# mosfet_shield.net
KiCad netlist of a schematic drawn in EAGLE
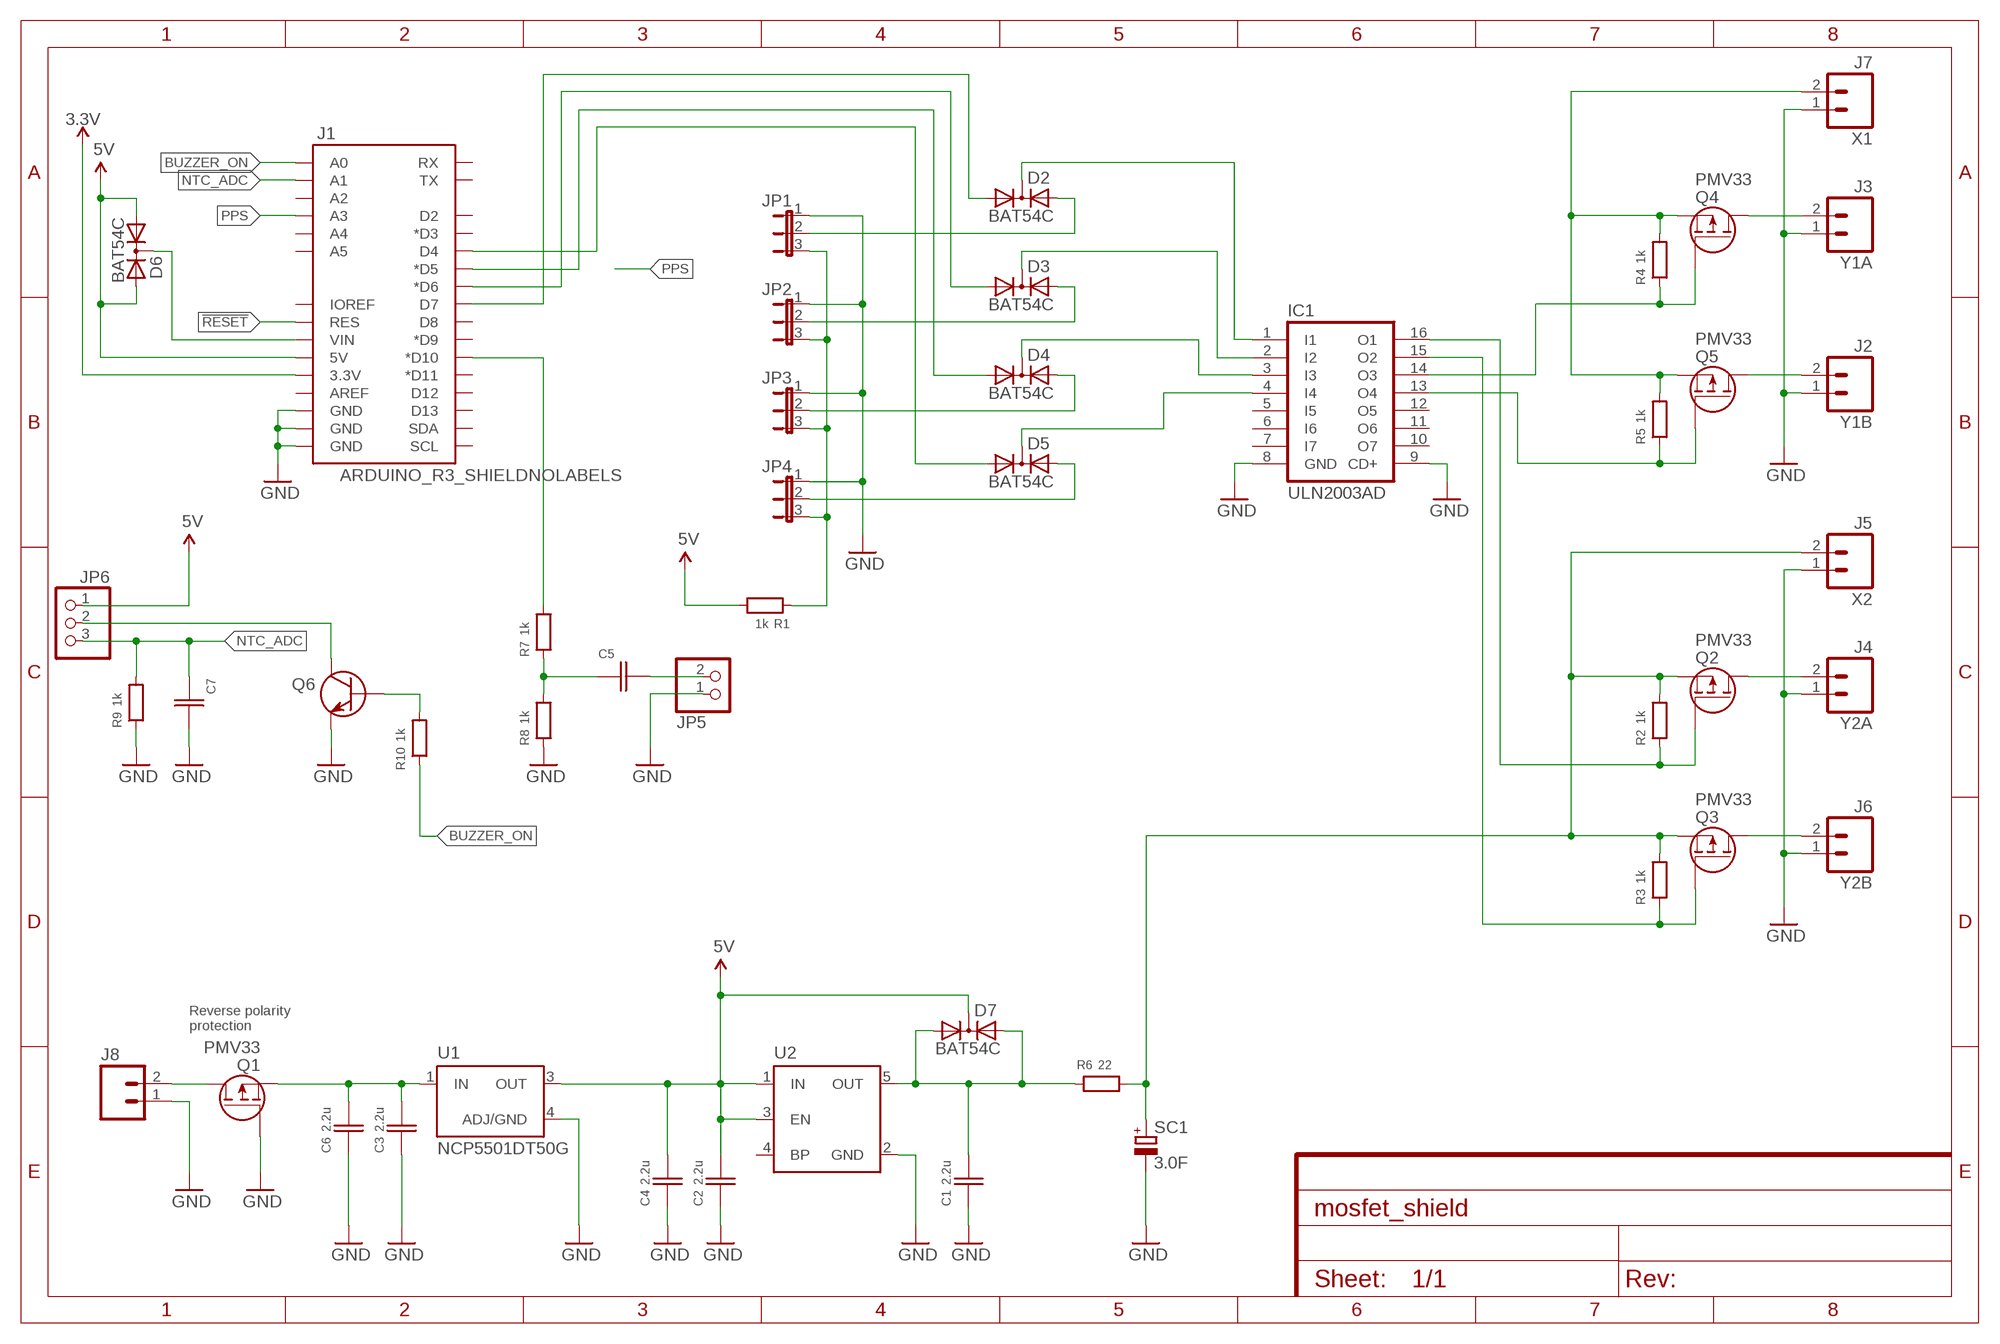
[diagram p0: schematic, sheet 1]

(export (version "E")
  (design (tool "Eeschema 10.0.6"))
  (components
    (comp (ref "C1")
      (value "2.2u")
      (footprint "eagle-import:C1206")
      (libsource (lib "eagle-import") (part "CAPACITOR_NPOL-1206"))
    )
    (comp (ref "C2")
      (value "2.2u")
      (footprint "eagle-import:C1206")
      (libsource (lib "eagle-import") (part "CAPACITOR_NPOL-1206"))
    )
    (comp (ref "C3")
      (value "2.2u")
      (footprint "eagle-import:C1206")
      (libsource (lib "eagle-import") (part "CAPACITOR_NPOL-1206"))
    )
    (comp (ref "C4")
      (value "2.2u")
      (footprint "eagle-import:C1206")
      (libsource (lib "eagle-import") (part "CAPACITOR_NPOL-1206"))
    )
    (comp (ref "C5")
      (value "CAPACITOR_NPOL-0603")
      (footprint "eagle-import:C603")
      (libsource (lib "eagle-import") (part "CAPACITOR_NPOL-0603"))
    )
    (comp (ref "C6")
      (value "2.2u")
      (footprint "eagle-import:C1206")
      (libsource (lib "eagle-import") (part "CAPACITOR_NPOL-1206"))
    )
    (comp (ref "C7")
      (value "CAPACITOR_NPOL-0603")
      (footprint "eagle-import:C603")
      (libsource (lib "eagle-import") (part "CAPACITOR_NPOL-0603"))
    )
    (comp (ref "D2")
      (value "BAT54C")
      (footprint "eagle-import:SOT23")
      (libsource (lib "eagle-import") (part "DIODE-2AC|CASOT23"))
    )
    (comp (ref "D3")
      (value "BAT54C")
      (footprint "eagle-import:SOT23")
      (libsource (lib "eagle-import") (part "DIODE-2AC|CASOT23"))
    )
    (comp (ref "D4")
      (value "BAT54C")
      (footprint "eagle-import:SOT23")
      (libsource (lib "eagle-import") (part "DIODE-2AC|CASOT23"))
    )
    (comp (ref "D5")
      (value "BAT54C")
      (footprint "eagle-import:SOT23")
      (libsource (lib "eagle-import") (part "DIODE-2AC|CASOT23"))
    )
    (comp (ref "D6")
      (value "BAT54C")
      (footprint "eagle-import:SOT23")
      (libsource (lib "eagle-import") (part "DIODE-2AC|CASOT23"))
    )
    (comp (ref "D7")
      (value "BAT54C")
      (footprint "eagle-import:SOT23")
      (libsource (lib "eagle-import") (part "DIODE-2AC|CASOT23"))
    )
    (comp (ref "IC1")
      (value "ULN2003AD")
      (footprint "eagle-import:SO16")
      (libsource (lib "eagle-import") (part "ULN2003AD"))
    )
    (comp (ref "J1")
      (value "ARDUINO_R3_SHIELDNOLABELS")
      (footprint "eagle-import:UNO_R3_SHIELD_NOLABELS")
      (libsource (lib "eagle-import") (part "ARDUINO_R3_SHIELDNOLABELS"))
    )
    (comp (ref "J2")
      (value "Y1B")
      (footprint "eagle-import:SCREWTERMINAL-3.5MM-2")
      (libsource (lib "eagle-import") (part "M023.5MM"))
    )
    (comp (ref "J3")
      (value "Y1A")
      (footprint "eagle-import:SCREWTERMINAL-3.5MM-2")
      (libsource (lib "eagle-import") (part "M023.5MM"))
    )
    (comp (ref "J4")
      (value "Y2A")
      (footprint "eagle-import:SCREWTERMINAL-3.5MM-2")
      (libsource (lib "eagle-import") (part "M023.5MM"))
    )
    (comp (ref "J5")
      (value "X2")
      (footprint "eagle-import:SCREWTERMINAL-3.5MM-2")
      (libsource (lib "eagle-import") (part "M023.5MM"))
    )
    (comp (ref "J6")
      (value "Y2B")
      (footprint "eagle-import:SCREWTERMINAL-3.5MM-2")
      (libsource (lib "eagle-import") (part "M023.5MM"))
    )
    (comp (ref "J7")
      (value "X1")
      (footprint "eagle-import:SCREWTERMINAL-3.5MM-2")
      (libsource (lib "eagle-import") (part "M023.5MM"))
    )
    (comp (ref "J8")
      (value "M023.5MM")
      (footprint "eagle-import:SCREWTERMINAL-3.5MM-2")
      (libsource (lib "eagle-import") (part "M023.5MM"))
    )
    (comp (ref "JP1")
      (value "JP2E")
      (footprint "eagle-import:JP2")
      (libsource (lib "eagle-import") (part "JP2E"))
    )
    (comp (ref "JP2")
      (value "JP2E")
      (footprint "eagle-import:JP2")
      (libsource (lib "eagle-import") (part "JP2E"))
    )
    (comp (ref "JP3")
      (value "JP2E")
      (footprint "eagle-import:JP2")
      (libsource (lib "eagle-import") (part "JP2E"))
    )
    (comp (ref "JP4")
      (value "JP2E")
      (footprint "eagle-import:JP2")
      (libsource (lib "eagle-import") (part "JP2E"))
    )
    (comp (ref "JP5")
      (value "PINHD-1X2")
      (footprint "eagle-import:1X02")
      (libsource (lib "eagle-import") (part "PINHD-1X2"))
    )
    (comp (ref "JP6")
      (value "PINHD-1X3")
      (footprint "eagle-import:1X03")
      (libsource (lib "eagle-import") (part "PINHD-1X3"))
    )
    (comp (ref "Q1")
      (value "PMV33")
      (footprint "eagle-import:SOT23-3")
      (libsource (lib "eagle-import") (part "MOSFET-P-SOT23-3"))
    )
    (comp (ref "Q2")
      (value "PMV33")
      (footprint "eagle-import:SOT23-3")
      (libsource (lib "eagle-import") (part "MOSFET-P-SOT23-3"))
    )
    (comp (ref "Q3")
      (value "PMV33")
      (footprint "eagle-import:SOT23-3")
      (libsource (lib "eagle-import") (part "MOSFET-P-SOT23-3"))
    )
    (comp (ref "Q4")
      (value "PMV33")
      (footprint "eagle-import:SOT23-3")
      (libsource (lib "eagle-import") (part "MOSFET-P-SOT23-3"))
    )
    (comp (ref "Q5")
      (value "PMV33")
      (footprint "eagle-import:SOT23-3")
      (libsource (lib "eagle-import") (part "MOSFET-P-SOT23-3"))
    )
    (comp (ref "Q6")
      (value "BJT-NPN-SOT23-3")
      (footprint "eagle-import:SOT23-3")
      (libsource (lib "eagle-import") (part "BJT-NPN-SOT23-3"))
    )
    (comp (ref "R1")
      (value "1k")
      (footprint "eagle-import:R0603")
      (libsource (lib "eagle-import") (part "RESISTOR-0603"))
    )
    (comp (ref "R2")
      (value "1k")
      (footprint "eagle-import:R0603")
      (libsource (lib "eagle-import") (part "RESISTOR-0603"))
    )
    (comp (ref "R3")
      (value "1k")
      (footprint "eagle-import:R0603")
      (libsource (lib "eagle-import") (part "RESISTOR-0603"))
    )
    (comp (ref "R4")
      (value "1k")
      (footprint "eagle-import:R0603")
      (libsource (lib "eagle-import") (part "RESISTOR-0603"))
    )
    (comp (ref "R5")
      (value "1k")
      (footprint "eagle-import:R0603")
      (libsource (lib "eagle-import") (part "RESISTOR-0603"))
    )
    (comp (ref "R6")
      (value "22")
      (footprint "eagle-import:R0603")
      (libsource (lib "eagle-import") (part "RESISTOR-0603"))
    )
    (comp (ref "R7")
      (value "1k")
      (footprint "eagle-import:R0603")
      (libsource (lib "eagle-import") (part "RESISTOR-0603"))
    )
    (comp (ref "R8")
      (value "1k")
      (footprint "eagle-import:R0603")
      (libsource (lib "eagle-import") (part "RESISTOR-0603"))
    )
    (comp (ref "R9")
      (value "1k")
      (footprint "eagle-import:R0603")
      (libsource (lib "eagle-import") (part "RESISTOR-0603"))
    )
    (comp (ref "R10")
      (value "1k")
      (footprint "eagle-import:R0603")
      (libsource (lib "eagle-import") (part "RESISTOR-0603"))
    )
    (comp (ref "SC1")
      (value "3.0F")
      (footprint "eagle-import:E3,5-8")
      (libsource (lib "eagle-import") (part "CPOL-EUE3.5-8"))
    )
    (comp (ref "U1")
      (value "NCP5501DT50G")
      (footprint "eagle-import:DPAK")
      (libsource (lib "eagle-import") (part "VREG-3PIN-DPAK"))
    )
    (comp (ref "U2")
      (value "VREG-5PIN-SOT23")
      (footprint "eagle-import:SOT23-5")
      (libsource (lib "eagle-import") (part "VREG-5PIN-SOT23"))
    )
  )
  (nets
    (net (code "1") (name "/~{RESET}") (class "Default")
      (node (ref "J1") (pin "RES") (pinfunction "RES_RES") (pintype "bidirectional"))
    )
    (net (code "2") (name "3.3V") (class "Default")
      (node (ref "J1") (pin "3.3V") (pinfunction "3.3V_3.3V") (pintype "bidirectional"))
    )
    (net (code "3") (name "5V") (class "Default")
      (node (ref "C2") (pin "2") (pinfunction "2_2") (pintype "passive"))
      (node (ref "C4") (pin "2") (pinfunction "2_2") (pintype "passive"))
      (node (ref "D6") (pin "1") (pinfunction "A1_1") (pintype "passive"))
      (node (ref "D6") (pin "2") (pinfunction "A2_2") (pintype "passive"))
      (node (ref "D7") (pin "3") (pinfunction "C_3") (pintype "passive"))
      (node (ref "J1") (pin "5V") (pinfunction "5V_5V") (pintype "bidirectional"))
      (node (ref "JP6") (pin "1") (pinfunction "1_1") (pintype "passive"))
      (node (ref "R1") (pin "2") (pinfunction "2_2") (pintype "passive"))
      (node (ref "U1") (pin "3") (pinfunction "OUT_3") (pintype "bidirectional"))
      (node (ref "U2") (pin "1") (pinfunction "IN_1") (pintype "bidirectional"))
      (node (ref "U2") (pin "3") (pinfunction "EN_3") (pintype "bidirectional"))
    )
    (net (code "4") (name "BUZZER_ON") (class "Default")
      (node (ref "J1") (pin "A0") (pinfunction "A0_A0") (pintype "bidirectional"))
      (node (ref "R10") (pin "1") (pinfunction "1_1") (pintype "passive"))
    )
    (net (code "5") (name "GND") (class "Default")
      (node (ref "C1") (pin "1") (pinfunction "1_1") (pintype "passive"))
      (node (ref "C2") (pin "1") (pinfunction "1_1") (pintype "passive"))
      (node (ref "C3") (pin "1") (pinfunction "1_1") (pintype "passive"))
      (node (ref "C4") (pin "1") (pinfunction "1_1") (pintype "passive"))
      (node (ref "C6") (pin "1") (pinfunction "1_1") (pintype "passive"))
      (node (ref "C7") (pin "2") (pinfunction "2_2") (pintype "passive"))
      (node (ref "IC1") (pin "8") (pinfunction "GND_8") (pintype "power_in"))
      (node (ref "IC1") (pin "9") (pinfunction "CD+_9") (pintype "passive"))
      (node (ref "J1") (pin "GND@0") (pinfunction "GND_GND@0") (pintype "bidirectional"))
      (node (ref "J1") (pin "GND@1") (pinfunction "GND_GND@1") (pintype "bidirectional"))
      (node (ref "J1") (pin "GND@2") (pinfunction "GND_GND@2") (pintype "bidirectional"))
      (node (ref "J2") (pin "1") (pinfunction "1_1") (pintype "passive"))
      (node (ref "J3") (pin "1") (pinfunction "1_1") (pintype "passive"))
      (node (ref "J4") (pin "1") (pinfunction "1_1") (pintype "passive"))
      (node (ref "J5") (pin "1") (pinfunction "1_1") (pintype "passive"))
      (node (ref "J6") (pin "1") (pinfunction "1_1") (pintype "passive"))
      (node (ref "J7") (pin "1") (pinfunction "1_1") (pintype "passive"))
      (node (ref "J8") (pin "1") (pinfunction "1_1") (pintype "passive"))
      (node (ref "JP1") (pin "1") (pinfunction "1_1") (pintype "passive"))
      (node (ref "JP2") (pin "1") (pinfunction "1_1") (pintype "passive"))
      (node (ref "JP3") (pin "1") (pinfunction "1_1") (pintype "passive"))
      (node (ref "JP4") (pin "1") (pinfunction "1_1") (pintype "passive"))
      (node (ref "JP5") (pin "1") (pinfunction "1_1") (pintype "passive"))
      (node (ref "Q1") (pin "1") (pinfunction "G_1") (pintype "passive"))
      (node (ref "Q6") (pin "2") (pinfunction "E_2") (pintype "passive"))
      (node (ref "R8") (pin "1") (pinfunction "1_1") (pintype "passive"))
      (node (ref "R9") (pin "1") (pinfunction "1_1") (pintype "passive"))
      (node (ref "SC1") (pin "-") (pinfunction "-_-") (pintype "passive"))
      (node (ref "U1") (pin "4") (pinfunction "ADJ/GND_4") (pintype "bidirectional"))
      (node (ref "U2") (pin "2") (pinfunction "GND_2") (pintype "bidirectional"))
    )
    (net (code "6") (name "NTC_ADC") (class "Default")
      (node (ref "C7") (pin "1") (pinfunction "1_1") (pintype "passive"))
      (node (ref "J1") (pin "A1") (pinfunction "A1_A1") (pintype "bidirectional"))
      (node (ref "JP6") (pin "3") (pinfunction "3_3") (pintype "passive"))
      (node (ref "R9") (pin "2") (pinfunction "2_2") (pintype "passive"))
    )
    (net (code "7") (name "Net-(C5-Pad1)") (class "Default")
      (node (ref "C5") (pin "1") (pinfunction "1_1") (pintype "passive"))
      (node (ref "R7") (pin "1") (pinfunction "1_1") (pintype "passive"))
      (node (ref "R8") (pin "2") (pinfunction "2_2") (pintype "passive"))
    )
    (net (code "8") (name "Net-(C5-Pad2)") (class "Default")
      (node (ref "C5") (pin "2") (pinfunction "2_2") (pintype "passive"))
      (node (ref "JP5") (pin "2") (pinfunction "2_2") (pintype "passive"))
    )
    (net (code "9") (name "Net-(D2-A1)") (class "Default")
      (node (ref "D2") (pin "1") (pinfunction "A1_1") (pintype "passive"))
      (node (ref "J1") (pin "D7") (pinfunction "D7_D7") (pintype "bidirectional"))
    )
    (net (code "10") (name "Net-(D2-A2)") (class "Default")
      (node (ref "D2") (pin "2") (pinfunction "A2_2") (pintype "passive"))
      (node (ref "JP1") (pin "2") (pinfunction "2_2") (pintype "passive"))
    )
    (net (code "11") (name "Net-(D2-C)") (class "Default")
      (node (ref "D2") (pin "3") (pinfunction "C_3") (pintype "passive"))
      (node (ref "IC1") (pin "1") (pinfunction "I1_1") (pintype "input"))
    )
    (net (code "12") (name "Net-(D3-A1)") (class "Default")
      (node (ref "D3") (pin "1") (pinfunction "A1_1") (pintype "passive"))
      (node (ref "J1") (pin "D6") (pinfunction "*D6_D6") (pintype "bidirectional"))
    )
    (net (code "13") (name "Net-(D3-A2)") (class "Default")
      (node (ref "D3") (pin "2") (pinfunction "A2_2") (pintype "passive"))
      (node (ref "JP2") (pin "2") (pinfunction "2_2") (pintype "passive"))
    )
    (net (code "14") (name "Net-(D3-C)") (class "Default")
      (node (ref "D3") (pin "3") (pinfunction "C_3") (pintype "passive"))
      (node (ref "IC1") (pin "2") (pinfunction "I2_2") (pintype "input"))
    )
    (net (code "15") (name "Net-(D4-A1)") (class "Default")
      (node (ref "D4") (pin "1") (pinfunction "A1_1") (pintype "passive"))
      (node (ref "J1") (pin "D5") (pinfunction "*D5_D5") (pintype "bidirectional"))
    )
    (net (code "16") (name "Net-(D4-A2)") (class "Default")
      (node (ref "D4") (pin "2") (pinfunction "A2_2") (pintype "passive"))
      (node (ref "JP3") (pin "2") (pinfunction "2_2") (pintype "passive"))
    )
    (net (code "17") (name "Net-(D4-C)") (class "Default")
      (node (ref "D4") (pin "3") (pinfunction "C_3") (pintype "passive"))
      (node (ref "IC1") (pin "3") (pinfunction "I3_3") (pintype "input"))
    )
    (net (code "18") (name "Net-(D5-A1)") (class "Default")
      (node (ref "D5") (pin "1") (pinfunction "A1_1") (pintype "passive"))
      (node (ref "J1") (pin "D4") (pinfunction "D4_D4") (pintype "bidirectional"))
    )
    (net (code "19") (name "Net-(D5-A2)") (class "Default")
      (node (ref "D5") (pin "2") (pinfunction "A2_2") (pintype "passive"))
      (node (ref "JP4") (pin "2") (pinfunction "2_2") (pintype "passive"))
    )
    (net (code "20") (name "Net-(D5-C)") (class "Default")
      (node (ref "D5") (pin "3") (pinfunction "C_3") (pintype "passive"))
      (node (ref "IC1") (pin "4") (pinfunction "I4_4") (pintype "input"))
    )
    (net (code "21") (name "Net-(D6-C)") (class "Default")
      (node (ref "D6") (pin "3") (pinfunction "C_3") (pintype "passive"))
      (node (ref "J1") (pin "VIN") (pinfunction "VIN_VIN") (pintype "bidirectional"))
    )
    (net (code "22") (name "Net-(D7-A1)") (class "Default")
      (node (ref "C1") (pin "2") (pinfunction "2_2") (pintype "passive"))
      (node (ref "D7") (pin "1") (pinfunction "A1_1") (pintype "passive"))
      (node (ref "D7") (pin "2") (pinfunction "A2_2") (pintype "passive"))
      (node (ref "R6") (pin "1") (pinfunction "1_1") (pintype "passive"))
      (node (ref "U2") (pin "5") (pinfunction "OUT_5") (pintype "bidirectional"))
    )
    (net (code "23") (name "Net-(IC1-O1)") (class "Default")
      (node (ref "IC1") (pin "16") (pinfunction "O1_16") (pintype "open_collector"))
      (node (ref "Q2") (pin "1") (pinfunction "G_1") (pintype "passive"))
      (node (ref "R2") (pin "1") (pinfunction "1_1") (pintype "passive"))
    )
    (net (code "24") (name "Net-(IC1-O2)") (class "Default")
      (node (ref "IC1") (pin "15") (pinfunction "O2_15") (pintype "open_collector"))
      (node (ref "Q3") (pin "1") (pinfunction "G_1") (pintype "passive"))
      (node (ref "R3") (pin "1") (pinfunction "1_1") (pintype "passive"))
    )
    (net (code "25") (name "Net-(IC1-O3)") (class "Default")
      (node (ref "IC1") (pin "14") (pinfunction "O3_14") (pintype "open_collector"))
      (node (ref "Q4") (pin "1") (pinfunction "G_1") (pintype "passive"))
      (node (ref "R4") (pin "1") (pinfunction "1_1") (pintype "passive"))
    )
    (net (code "26") (name "Net-(IC1-O4)") (class "Default")
      (node (ref "IC1") (pin "13") (pinfunction "O4_13") (pintype "open_collector"))
      (node (ref "Q5") (pin "1") (pinfunction "G_1") (pintype "passive"))
      (node (ref "R5") (pin "1") (pinfunction "1_1") (pintype "passive"))
    )
    (net (code "27") (name "Net-(J1-*D10)") (class "Default")
      (node (ref "J1") (pin "D10") (pinfunction "*D10_D10") (pintype "bidirectional"))
      (node (ref "R7") (pin "2") (pinfunction "2_2") (pintype "passive"))
    )
    (net (code "28") (name "Net-(JP1-Pad3)") (class "Default")
      (node (ref "JP1") (pin "3") (pinfunction "3_3") (pintype "passive"))
      (node (ref "JP2") (pin "3") (pinfunction "3_3") (pintype "passive"))
      (node (ref "JP3") (pin "3") (pinfunction "3_3") (pintype "passive"))
      (node (ref "JP4") (pin "3") (pinfunction "3_3") (pintype "passive"))
      (node (ref "R1") (pin "1") (pinfunction "1_1") (pintype "passive"))
    )
    (net (code "29") (name "Net-(Q1-D)") (class "Default")
      (node (ref "J8") (pin "2") (pinfunction "2_2") (pintype "passive"))
      (node (ref "Q1") (pin "3") (pinfunction "D_3") (pintype "passive"))
    )
    (net (code "30") (name "Net-(Q1-S)") (class "Default")
      (node (ref "C3") (pin "2") (pinfunction "2_2") (pintype "passive"))
      (node (ref "C6") (pin "2") (pinfunction "2_2") (pintype "passive"))
      (node (ref "Q1") (pin "2") (pinfunction "S_2") (pintype "passive"))
      (node (ref "U1") (pin "1") (pinfunction "IN_1") (pintype "bidirectional"))
    )
    (net (code "31") (name "Net-(Q2-D)") (class "Default")
      (node (ref "J4") (pin "2") (pinfunction "2_2") (pintype "passive"))
      (node (ref "Q2") (pin "3") (pinfunction "D_3") (pintype "passive"))
    )
    (net (code "32") (name "Net-(Q2-S)") (class "Default")
      (node (ref "J5") (pin "2") (pinfunction "2_2") (pintype "passive"))
      (node (ref "Q2") (pin "2") (pinfunction "S_2") (pintype "passive"))
      (node (ref "Q3") (pin "2") (pinfunction "S_2") (pintype "passive"))
      (node (ref "R2") (pin "2") (pinfunction "2_2") (pintype "passive"))
      (node (ref "R3") (pin "2") (pinfunction "2_2") (pintype "passive"))
      (node (ref "R6") (pin "2") (pinfunction "2_2") (pintype "passive"))
      (node (ref "SC1") (pin "+") (pinfunction "+_+") (pintype "passive"))
    )
    (net (code "33") (name "Net-(Q3-D)") (class "Default")
      (node (ref "J6") (pin "2") (pinfunction "2_2") (pintype "passive"))
      (node (ref "Q3") (pin "3") (pinfunction "D_3") (pintype "passive"))
    )
    (net (code "34") (name "Net-(Q4-D)") (class "Default")
      (node (ref "J3") (pin "2") (pinfunction "2_2") (pintype "passive"))
      (node (ref "Q4") (pin "3") (pinfunction "D_3") (pintype "passive"))
    )
    (net (code "35") (name "Net-(Q4-S)") (class "Default")
      (node (ref "J7") (pin "2") (pinfunction "2_2") (pintype "passive"))
      (node (ref "Q4") (pin "2") (pinfunction "S_2") (pintype "passive"))
      (node (ref "Q5") (pin "2") (pinfunction "S_2") (pintype "passive"))
      (node (ref "R4") (pin "2") (pinfunction "2_2") (pintype "passive"))
      (node (ref "R5") (pin "2") (pinfunction "2_2") (pintype "passive"))
    )
    (net (code "36") (name "Net-(Q5-D)") (class "Default")
      (node (ref "J2") (pin "2") (pinfunction "2_2") (pintype "passive"))
      (node (ref "Q5") (pin "3") (pinfunction "D_3") (pintype "passive"))
    )
    (net (code "37") (name "Net-(Q6-B)") (class "Default")
      (node (ref "Q6") (pin "1") (pinfunction "B_1") (pintype "passive"))
      (node (ref "R10") (pin "2") (pinfunction "2_2") (pintype "passive"))
    )
    (net (code "38") (name "Net-(Q6-C)") (class "Default")
      (node (ref "JP6") (pin "2") (pinfunction "2_2") (pintype "passive"))
      (node (ref "Q6") (pin "3") (pinfunction "C_3") (pintype "passive"))
    )
    (net (code "39") (name "PPS") (class "Default")
      (node (ref "J1") (pin "A3") (pinfunction "A3_A3") (pintype "bidirectional"))
    )
    (net (code "40") (name "unconnected-(IC1-I5-Pad5)") (class "Default")
      (node (ref "IC1") (pin "5") (pinfunction "I5_5") (pintype "input"))
    )
    (net (code "41") (name "unconnected-(IC1-I6-Pad6)") (class "Default")
      (node (ref "IC1") (pin "6") (pinfunction "I6_6") (pintype "input"))
    )
    (net (code "42") (name "unconnected-(IC1-I7-Pad7)") (class "Default")
      (node (ref "IC1") (pin "7") (pinfunction "I7_7") (pintype "input"))
    )
    (net (code "43") (name "unconnected-(IC1-O5-Pad12)") (class "Default")
      (node (ref "IC1") (pin "12") (pinfunction "O5_12") (pintype "open_collector"))
    )
    (net (code "44") (name "unconnected-(IC1-O6-Pad11)") (class "Default")
      (node (ref "IC1") (pin "11") (pinfunction "O6_11") (pintype "open_collector"))
    )
    (net (code "45") (name "unconnected-(IC1-O7-Pad10)") (class "Default")
      (node (ref "IC1") (pin "10") (pinfunction "O7_10") (pintype "open_collector"))
    )
    (net (code "46") (name "unconnected-(J1-*D3-PadD3)") (class "Default")
      (node (ref "J1") (pin "D3") (pinfunction "*D3_D3") (pintype "bidirectional"))
    )
    (net (code "47") (name "unconnected-(J1-*D9-PadD9)") (class "Default")
      (node (ref "J1") (pin "D9") (pinfunction "*D9_D9") (pintype "bidirectional"))
    )
    (net (code "48") (name "unconnected-(J1-*D11-PadD11)") (class "Default")
      (node (ref "J1") (pin "D11") (pinfunction "*D11_D11") (pintype "bidirectional"))
    )
    (net (code "49") (name "unconnected-(J1-PadA2)") (class "Default")
      (node (ref "J1") (pin "A2") (pinfunction "A2_A2") (pintype "bidirectional"))
    )
    (net (code "50") (name "unconnected-(J1-PadA4)") (class "Default")
      (node (ref "J1") (pin "A4") (pinfunction "A4_A4") (pintype "bidirectional"))
    )
    (net (code "51") (name "unconnected-(J1-PadA5)") (class "Default")
      (node (ref "J1") (pin "A5") (pinfunction "A5_A5") (pintype "bidirectional"))
    )
    (net (code "52") (name "unconnected-(J1-PadAREF)") (class "Default")
      (node (ref "J1") (pin "AREF") (pinfunction "AREF_AREF") (pintype "bidirectional"))
    )
    (net (code "53") (name "unconnected-(J1-PadD2)") (class "Default")
      (node (ref "J1") (pin "D2") (pinfunction "D2_D2") (pintype "bidirectional"))
    )
    (net (code "54") (name "unconnected-(J1-PadD8)") (class "Default")
      (node (ref "J1") (pin "D8") (pinfunction "D8_D8") (pintype "bidirectional"))
    )
    (net (code "55") (name "unconnected-(J1-PadD12)") (class "Default")
      (node (ref "J1") (pin "D12") (pinfunction "D12_D12") (pintype "bidirectional"))
    )
    (net (code "56") (name "unconnected-(J1-PadD13)") (class "Default")
      (node (ref "J1") (pin "D13") (pinfunction "D13_D13") (pintype "bidirectional"))
    )
    (net (code "57") (name "unconnected-(J1-PadIOREF)") (class "Default")
      (node (ref "J1") (pin "IOREF") (pinfunction "IOREF_IOREF") (pintype "bidirectional"))
    )
    (net (code "58") (name "unconnected-(J1-PadRX)") (class "Default")
      (node (ref "J1") (pin "RX") (pinfunction "RX_RX") (pintype "bidirectional"))
    )
    (net (code "59") (name "unconnected-(J1-PadSCL)") (class "Default")
      (node (ref "J1") (pin "SCL") (pinfunction "SCL_SCL") (pintype "bidirectional"))
    )
    (net (code "60") (name "unconnected-(J1-PadSDA)") (class "Default")
      (node (ref "J1") (pin "SDA") (pinfunction "SDA_SDA") (pintype "bidirectional"))
    )
    (net (code "61") (name "unconnected-(J1-PadTX)") (class "Default")
      (node (ref "J1") (pin "TX") (pinfunction "TX_TX") (pintype "bidirectional"))
    )
    (net (code "62") (name "unconnected-(U2-BP-Pad4)") (class "Default")
      (node (ref "U2") (pin "4") (pinfunction "BP_4") (pintype "bidirectional"))
    )
  )
)
